# led4pins.net
KiCad netlist of a schematic drawn in EAGLE
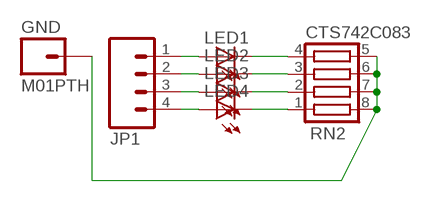
[diagram p0: schematic, sheet 1]

(export (version "E")
  (design (tool "Eeschema 10.0.6"))
  (components
    (comp (ref "GND")
      (value "M01PTH")
      (footprint "eagle-import:1X01")
      (libsource (lib "eagle-import") (part "M01PTH"))
    )
    (comp (ref "JP1")
      (value "M04PTH")
      (footprint "eagle-import:1X04")
      (libsource (lib "eagle-import") (part "M04PTH"))
    )
    (comp (ref "LED1")
      (value "LEDCHIP-LED0603")
      (footprint "eagle-import:CHIP-LED0603")
      (libsource (lib "eagle-import") (part "LEDCHIP-LED0603"))
    )
    (comp (ref "LED2")
      (value "LEDCHIP-LED0603")
      (footprint "eagle-import:CHIP-LED0603")
      (libsource (lib "eagle-import") (part "LEDCHIP-LED0603"))
    )
    (comp (ref "LED3")
      (value "LEDCHIP-LED0603")
      (footprint "eagle-import:CHIP-LED0603")
      (libsource (lib "eagle-import") (part "LEDCHIP-LED0603"))
    )
    (comp (ref "LED4")
      (value "LEDCHIP-LED0603")
      (footprint "eagle-import:CHIP-LED0603")
      (libsource (lib "eagle-import") (part "LEDCHIP-LED0603"))
    )
    (comp (ref "RN2")
      (value "CTS742C083")
      (footprint "eagle-import:CTS742C083")
      (fields (field (name "OC_FARNELL") "unknown") (field (name "OC_NEWARK") "unknown"))
      (libsource (lib "eagle-import") (part "CTS742C083"))
    )
  )
  (nets
    (net (code "1") (name "Net-(GND-Pad1)") (class "Default")
      (node (ref "GND") (pin "1") (pinfunction "1_1") (pintype "passive"))
      (node (ref "RN2") (pin "5") (pinfunction "5_5") (pintype "passive"))
      (node (ref "RN2") (pin "6") (pinfunction "6_6") (pintype "passive"))
      (node (ref "RN2") (pin "7") (pinfunction "7_7") (pintype "passive"))
      (node (ref "RN2") (pin "8") (pinfunction "8_8") (pintype "passive"))
    )
    (net (code "2") (name "Net-(JP1-Pad1)") (class "Default")
      (node (ref "JP1") (pin "1") (pinfunction "1_1") (pintype "passive"))
      (node (ref "LED1") (pin "A") (pinfunction "A_A") (pintype "passive"))
    )
    (net (code "3") (name "Net-(JP1-Pad2)") (class "Default")
      (node (ref "JP1") (pin "2") (pinfunction "2_2") (pintype "passive"))
      (node (ref "LED2") (pin "A") (pinfunction "A_A") (pintype "passive"))
    )
    (net (code "4") (name "Net-(JP1-Pad3)") (class "Default")
      (node (ref "JP1") (pin "3") (pinfunction "3_3") (pintype "passive"))
      (node (ref "LED3") (pin "A") (pinfunction "A_A") (pintype "passive"))
    )
    (net (code "5") (name "Net-(JP1-Pad4)") (class "Default")
      (node (ref "JP1") (pin "4") (pinfunction "4_4") (pintype "passive"))
      (node (ref "LED4") (pin "A") (pinfunction "A_A") (pintype "passive"))
    )
    (net (code "6") (name "Net-(LED1-PadC)") (class "Default")
      (node (ref "LED1") (pin "C") (pinfunction "C_C") (pintype "passive"))
      (node (ref "RN2") (pin "4") (pinfunction "4_4") (pintype "passive"))
    )
    (net (code "7") (name "Net-(LED2-PadC)") (class "Default")
      (node (ref "LED2") (pin "C") (pinfunction "C_C") (pintype "passive"))
      (node (ref "RN2") (pin "3") (pinfunction "3_3") (pintype "passive"))
    )
    (net (code "8") (name "Net-(LED3-PadC)") (class "Default")
      (node (ref "LED3") (pin "C") (pinfunction "C_C") (pintype "passive"))
      (node (ref "RN2") (pin "2") (pinfunction "2_2") (pintype "passive"))
    )
    (net (code "9") (name "Net-(LED4-PadC)") (class "Default")
      (node (ref "LED4") (pin "C") (pinfunction "C_C") (pintype "passive"))
      (node (ref "RN2") (pin "1") (pinfunction "1_1") (pintype "passive"))
    )
  )
)
